# avrisp-level-transl.net
KiCad netlist of a schematic drawn in EAGLE
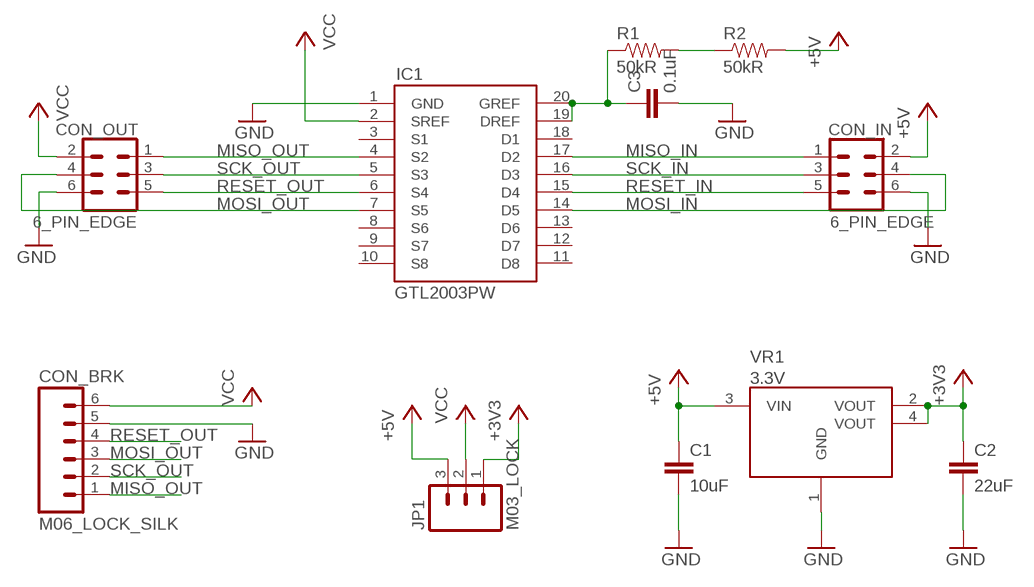
[diagram p0: schematic, sheet 1]

(export (version "E")
  (design (tool "Eeschema 10.0.6"))
  (components
    (comp (ref "C1")
      (value "10uF")
      (footprint "eagle-import:0805")
      (libsource (lib "eagle-import") (part "CAPACITOR0805"))
    )
    (comp (ref "C2")
      (value "22uF")
      (footprint "eagle-import:0805")
      (libsource (lib "eagle-import") (part "CAPACITOR0805"))
    )
    (comp (ref "C3")
      (value "0.1uF")
      (footprint "eagle-import:0805")
      (libsource (lib "eagle-import") (part "CAPACITOR0805"))
    )
    (comp (ref "CON_BRK")
      (value "M06_LOCK_SILK")
      (footprint "eagle-import:M06_LOCK_SILK")
      (libsource (lib "eagle-import") (part "M06_LOCK_SILK"))
    )
    (comp (ref "CON_IN")
      (value "6_PIN_EDGE")
      (footprint "eagle-import:6_PIN_EDGE")
      (libsource (lib "eagle-import") (part "6_PIN_EDGE"))
    )
    (comp (ref "CON_OUT")
      (value "6_PIN_EDGE")
      (footprint "eagle-import:6_PIN_EDGE")
      (libsource (lib "eagle-import") (part "6_PIN_EDGE"))
    )
    (comp (ref "IC1")
      (value "GTL2003PW")
      (footprint "eagle-import:TSSOP-20")
      (libsource (lib "eagle-import") (part "GTL2003PW"))
    )
    (comp (ref "JP1")
      (value "M03_LOCK")
      (footprint "eagle-import:M03_LOCK")
      (libsource (lib "eagle-import") (part "M03_LOCK"))
    )
    (comp (ref "R1")
      (value "50kR")
      (footprint "eagle-import:0805")
      (libsource (lib "eagle-import") (part "RESISTOR0805"))
    )
    (comp (ref "R2")
      (value "50kR")
      (footprint "eagle-import:0805")
      (libsource (lib "eagle-import") (part "RESISTOR0805"))
    )
    (comp (ref "VR1")
      (value "3.3V")
      (footprint "eagle-import:SOT223")
      (libsource (lib "eagle-import") (part "AMS1117_SOT223"))
    )
  )
  (nets
    (net (code "1") (name "+3V3") (class "Default")
      (node (ref "C2") (pin "1") (pinfunction "1_1") (pintype "passive"))
      (node (ref "JP1") (pin "1") (pinfunction "1_1") (pintype "passive"))
      (node (ref "VR1") (pin "2") (pinfunction "VOUT_2") (pintype "bidirectional"))
      (node (ref "VR1") (pin "4") (pinfunction "VOUT_4") (pintype "bidirectional"))
    )
    (net (code "2") (name "+5V") (class "Default")
      (node (ref "C1") (pin "1") (pinfunction "1_1") (pintype "passive"))
      (node (ref "CON_IN") (pin "2") (pinfunction "2_2") (pintype "passive"))
      (node (ref "JP1") (pin "3") (pinfunction "3_3") (pintype "passive"))
      (node (ref "R2") (pin "2") (pinfunction "2_2") (pintype "passive"))
      (node (ref "VR1") (pin "3") (pinfunction "VIN_3") (pintype "bidirectional"))
    )
    (net (code "3") (name "/MISO_IN") (class "Default")
      (node (ref "CON_IN") (pin "1") (pinfunction "1_1") (pintype "passive"))
      (node (ref "IC1") (pin "17") (pinfunction "D2_17") (pintype "bidirectional"))
    )
    (net (code "4") (name "/MISO_OUT") (class "Default")
      (node (ref "CON_BRK") (pin "1") (pinfunction "1_1") (pintype "passive"))
      (node (ref "CON_OUT") (pin "1") (pinfunction "1_1") (pintype "passive"))
      (node (ref "IC1") (pin "4") (pinfunction "S2_4") (pintype "bidirectional"))
    )
    (net (code "5") (name "/MOSI_IN") (class "Default")
      (node (ref "CON_IN") (pin "4") (pinfunction "4_4") (pintype "passive"))
      (node (ref "IC1") (pin "14") (pinfunction "D5_14") (pintype "bidirectional"))
    )
    (net (code "6") (name "/MOSI_OUT") (class "Default")
      (node (ref "CON_BRK") (pin "3") (pinfunction "3_3") (pintype "passive"))
      (node (ref "CON_OUT") (pin "4") (pinfunction "4_4") (pintype "passive"))
      (node (ref "IC1") (pin "7") (pinfunction "S5_7") (pintype "bidirectional"))
    )
    (net (code "7") (name "/RESET_IN") (class "Default")
      (node (ref "CON_IN") (pin "5") (pinfunction "5_5") (pintype "passive"))
      (node (ref "IC1") (pin "15") (pinfunction "D4_15") (pintype "bidirectional"))
    )
    (net (code "8") (name "/RESET_OUT") (class "Default")
      (node (ref "CON_BRK") (pin "4") (pinfunction "4_4") (pintype "passive"))
      (node (ref "CON_OUT") (pin "5") (pinfunction "5_5") (pintype "passive"))
      (node (ref "IC1") (pin "6") (pinfunction "S4_6") (pintype "bidirectional"))
    )
    (net (code "9") (name "/SCK_IN") (class "Default")
      (node (ref "CON_IN") (pin "3") (pinfunction "3_3") (pintype "passive"))
      (node (ref "IC1") (pin "16") (pinfunction "D3_16") (pintype "bidirectional"))
    )
    (net (code "10") (name "/SCK_OUT") (class "Default")
      (node (ref "CON_BRK") (pin "2") (pinfunction "2_2") (pintype "passive"))
      (node (ref "CON_OUT") (pin "3") (pinfunction "3_3") (pintype "passive"))
      (node (ref "IC1") (pin "5") (pinfunction "S3_5") (pintype "bidirectional"))
    )
    (net (code "11") (name "GND") (class "Default")
      (node (ref "C1") (pin "2") (pinfunction "2_2") (pintype "passive"))
      (node (ref "C2") (pin "2") (pinfunction "2_2") (pintype "passive"))
      (node (ref "C3") (pin "2") (pinfunction "2_2") (pintype "passive"))
      (node (ref "CON_BRK") (pin "5") (pinfunction "5_5") (pintype "passive"))
      (node (ref "CON_IN") (pin "6") (pinfunction "6_6") (pintype "passive"))
      (node (ref "CON_OUT") (pin "6") (pinfunction "6_6") (pintype "passive"))
      (node (ref "IC1") (pin "1") (pinfunction "GND_1") (pintype "bidirectional"))
      (node (ref "VR1") (pin "1") (pinfunction "GND_1") (pintype "bidirectional"))
    )
    (net (code "12") (name "Net-(IC1-DREF)") (class "Default")
      (node (ref "C3") (pin "1") (pinfunction "1_1") (pintype "passive"))
      (node (ref "IC1") (pin "19") (pinfunction "DREF_19") (pintype "bidirectional"))
      (node (ref "IC1") (pin "20") (pinfunction "GREF_20") (pintype "bidirectional"))
      (node (ref "R1") (pin "1") (pinfunction "1_1") (pintype "passive"))
    )
    (net (code "13") (name "Net-(R1-Pad2)") (class "Default")
      (node (ref "R1") (pin "2") (pinfunction "2_2") (pintype "passive"))
      (node (ref "R2") (pin "1") (pinfunction "1_1") (pintype "passive"))
    )
    (net (code "14") (name "VCC") (class "Default")
      (node (ref "CON_BRK") (pin "6") (pinfunction "6_6") (pintype "passive"))
      (node (ref "CON_OUT") (pin "2") (pinfunction "2_2") (pintype "passive"))
      (node (ref "IC1") (pin "2") (pinfunction "SREF_2") (pintype "bidirectional"))
      (node (ref "JP1") (pin "2") (pinfunction "2_2") (pintype "passive"))
    )
    (net (code "15") (name "unconnected-(IC1-D1-Pad18)") (class "Default")
      (node (ref "IC1") (pin "18") (pinfunction "D1_18") (pintype "bidirectional"))
    )
    (net (code "16") (name "unconnected-(IC1-D6-Pad13)") (class "Default")
      (node (ref "IC1") (pin "13") (pinfunction "D6_13") (pintype "bidirectional"))
    )
    (net (code "17") (name "unconnected-(IC1-D7-Pad12)") (class "Default")
      (node (ref "IC1") (pin "12") (pinfunction "D7_12") (pintype "bidirectional"))
    )
    (net (code "18") (name "unconnected-(IC1-D8-Pad11)") (class "Default")
      (node (ref "IC1") (pin "11") (pinfunction "D8_11") (pintype "bidirectional"))
    )
    (net (code "19") (name "unconnected-(IC1-S1-Pad3)") (class "Default")
      (node (ref "IC1") (pin "3") (pinfunction "S1_3") (pintype "bidirectional"))
    )
    (net (code "20") (name "unconnected-(IC1-S6-Pad8)") (class "Default")
      (node (ref "IC1") (pin "8") (pinfunction "S6_8") (pintype "bidirectional"))
    )
    (net (code "21") (name "unconnected-(IC1-S7-Pad9)") (class "Default")
      (node (ref "IC1") (pin "9") (pinfunction "S7_9") (pintype "bidirectional"))
    )
    (net (code "22") (name "unconnected-(IC1-S8-Pad10)") (class "Default")
      (node (ref "IC1") (pin "10") (pinfunction "S8_10") (pintype "bidirectional"))
    )
  )
)
